# Nimble.net
KiCad netlist of a schematic drawn in EAGLE
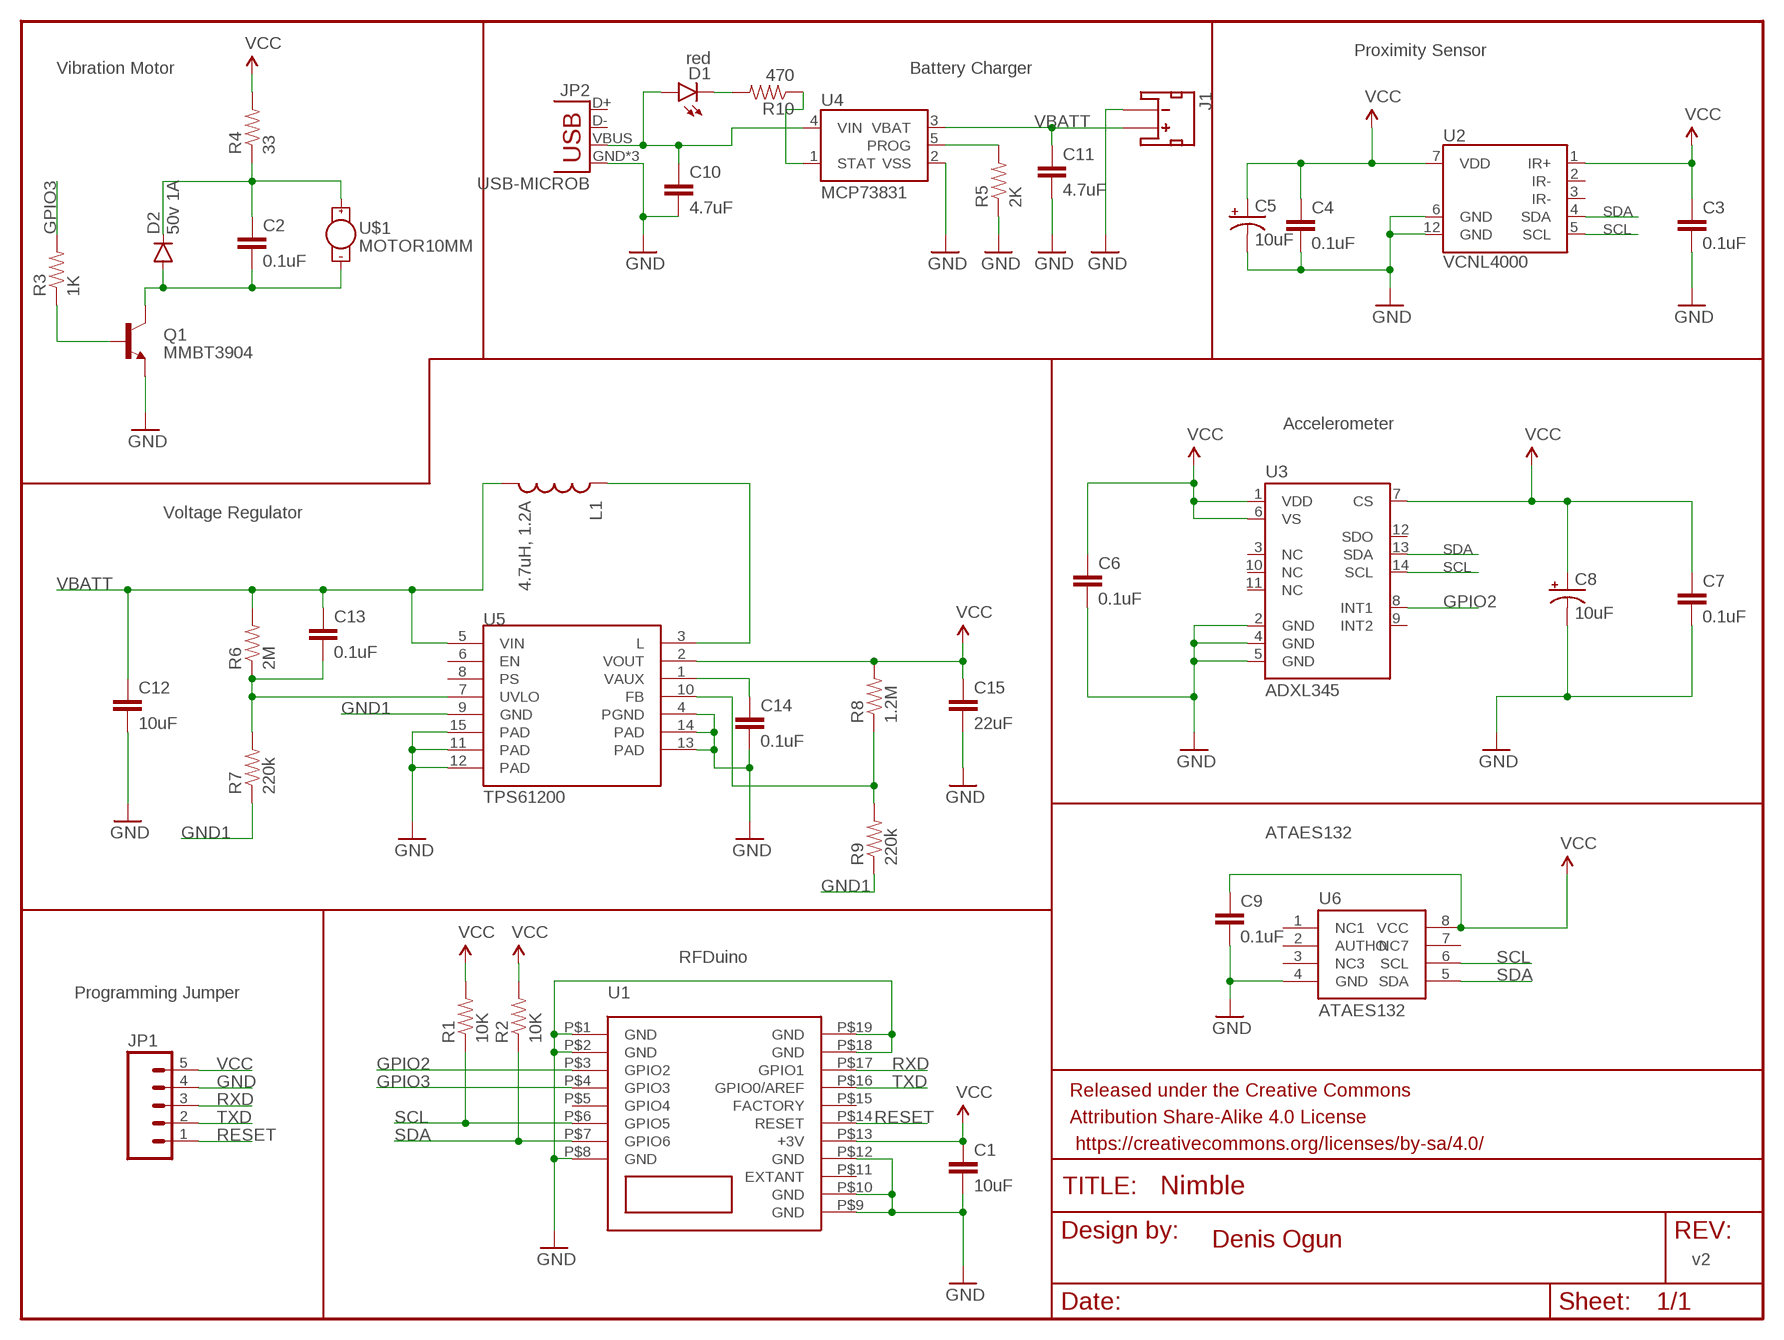
[diagram p0: schematic, sheet 1]

(export (version "E")
  (design (tool "Eeschema 10.0.6"))
  (components
    (comp (ref "C1")
      (value "10uF")
      (footprint "eagle-import:0603-CAP")
      (libsource (lib "eagle-import") (part "CAP0603-CAP"))
    )
    (comp (ref "C2")
      (value "0.1uF")
      (footprint "eagle-import:0603-CAP")
      (libsource (lib "eagle-import") (part "CAP0603-CAP"))
    )
    (comp (ref "C3")
      (value "0.1uF")
      (footprint "eagle-import:0603-CAP")
      (libsource (lib "eagle-import") (part "CAP0603-CAP"))
    )
    (comp (ref "C4")
      (value "0.1uF")
      (footprint "eagle-import:0603-CAP")
      (libsource (lib "eagle-import") (part "CAP0603-CAP"))
    )
    (comp (ref "C5")
      (value "10uF")
      (footprint "eagle-import:EIA3216")
      (libsource (lib "eagle-import") (part "CAP_POL1206"))
    )
    (comp (ref "C6")
      (value "0.1uF")
      (footprint "eagle-import:0603-CAP")
      (libsource (lib "eagle-import") (part "CAP0603-CAP"))
    )
    (comp (ref "C7")
      (value "0.1uF")
      (footprint "eagle-import:0603-CAP")
      (libsource (lib "eagle-import") (part "CAP0603-CAP"))
    )
    (comp (ref "C8")
      (value "10uF")
      (footprint "eagle-import:EIA3216")
      (libsource (lib "eagle-import") (part "CAP_POL1206"))
    )
    (comp (ref "C9")
      (value "0.1uF")
      (footprint "eagle-import:0603-CAP")
      (libsource (lib "eagle-import") (part "CAP0603-CAP"))
    )
    (comp (ref "C10")
      (value "4.7uF")
      (footprint "eagle-import:0603-CAP")
      (libsource (lib "eagle-import") (part "CAP0603-CAP"))
    )
    (comp (ref "C11")
      (value "4.7uF")
      (footprint "eagle-import:0603-CAP")
      (libsource (lib "eagle-import") (part "CAP0603-CAP"))
    )
    (comp (ref "C12")
      (value "10uF")
      (footprint "eagle-import:1206")
      (libsource (lib "eagle-import") (part "CAP1206"))
    )
    (comp (ref "C13")
      (value "0.1uF")
      (footprint "eagle-import:0603-CAP")
      (libsource (lib "eagle-import") (part "CAP0603-CAP"))
    )
    (comp (ref "C14")
      (value "0.1uF")
      (footprint "eagle-import:0603-CAP")
      (libsource (lib "eagle-import") (part "CAP0603-CAP"))
    )
    (comp (ref "C15")
      (value "22uF")
      (footprint "eagle-import:0805")
      (libsource (lib "eagle-import") (part "CAP0805"))
    )
    (comp (ref "D1")
      (value "red")
      (footprint "eagle-import:LED-0603")
      (libsource (lib "eagle-import") (part "LED0603"))
    )
    (comp (ref "D2")
      (value "50v 1A")
      (footprint "eagle-import:SMA-DIODE")
      (libsource (lib "eagle-import") (part "DIODESMA"))
    )
    (comp (ref "FRAME1")
      (value "FRAME-LETTERNO_PACKAGE")
      (footprint "eagle-import:DUMMY")
      (fields (field (name "DESIGNER") "Nobody"))
      (libsource (lib "eagle-import") (part "FRAME-LETTERNO_PACKAGE"))
    )
    (comp (ref "J1")
      (value "JST_2MM_MALE")
      (footprint "eagle-import:JST-2-SMD")
      (libsource (lib "eagle-import") (part "JST_2MM_MALE"))
    )
    (comp (ref "JP1")
      (value "M05PTH")
      (footprint "eagle-import:1X05")
      (libsource (lib "eagle-import") (part "M05PTH"))
    )
    (comp (ref "JP2")
      (value "USB-MICROB")
      (footprint "eagle-import:USB-MICROB")
      (libsource (lib "eagle-import") (part "USB-MICROB"))
    )
    (comp (ref "L1")
      (value "4.7uH, 1.2A")
      (footprint "eagle-import:CDRH2D09")
      (libsource (lib "eagle-import") (part "INDUCTOR."))
    )
    (comp (ref "Q1")
      (value "MMBT3904")
      (footprint "eagle-import:SOT23-3")
      (libsource (lib "eagle-import") (part "TRANSISTOR_NPNMMBT2222A"))
    )
    (comp (ref "R1")
      (value "10K")
      (footprint "eagle-import:0603-RES")
      (libsource (lib "eagle-import") (part "RESISTOR0603"))
    )
    (comp (ref "R2")
      (value "10K")
      (footprint "eagle-import:0603-RES")
      (libsource (lib "eagle-import") (part "RESISTOR0603"))
    )
    (comp (ref "R3")
      (value "1K")
      (footprint "eagle-import:0603-RES")
      (libsource (lib "eagle-import") (part "RESISTOR0603"))
    )
    (comp (ref "R4")
      (value "33")
      (footprint "eagle-import:0603-RES")
      (libsource (lib "eagle-import") (part "RESISTOR0603"))
    )
    (comp (ref "R5")
      (value "2K")
      (footprint "eagle-import:0603-RES")
      (libsource (lib "eagle-import") (part "RESISTOR0603"))
    )
    (comp (ref "R6")
      (value "2M")
      (footprint "eagle-import:0603-RES")
      (libsource (lib "eagle-import") (part "RESISTOR0603"))
    )
    (comp (ref "R7")
      (value "220k")
      (footprint "eagle-import:0603-RES")
      (libsource (lib "eagle-import") (part "RESISTOR0603"))
    )
    (comp (ref "R8")
      (value "1.2M")
      (footprint "eagle-import:0603-RES")
      (libsource (lib "eagle-import") (part "RESISTOR0603"))
    )
    (comp (ref "R9")
      (value "220k")
      (footprint "eagle-import:0603-RES")
      (libsource (lib "eagle-import") (part "RESISTOR0603"))
    )
    (comp (ref "R10")
      (value "470")
      (footprint "eagle-import:0603-RES")
      (libsource (lib "eagle-import") (part "RESISTOR0603"))
    )
    (comp (ref "U$1")
      (value "MOTOR10MM")
      (footprint "eagle-import:VIBE-MOTOR-10MM")
      (libsource (lib "eagle-import") (part "MOTOR10MM"))
    )
    (comp (ref "U1")
      (value "RFD22301")
      (footprint "eagle-import:RFD22301")
      (libsource (lib "eagle-import") (part "RFD22301"))
    )
    (comp (ref "U2")
      (value "VCNL4000")
      (footprint "eagle-import:VCNL4000")
      (libsource (lib "eagle-import") (part "VCNL4000"))
    )
    (comp (ref "U3")
      (value "ADXL345")
      (footprint "eagle-import:LGA14")
      (libsource (lib "eagle-import") (part "ADXL345"))
    )
    (comp (ref "U4")
      (value "MCP73831")
      (footprint "eagle-import:SOT23-5")
      (libsource (lib "eagle-import") (part "MCP73831"))
    )
    (comp (ref "U5")
      (value "TPS61200")
      (footprint "eagle-import:QFN-10_PAD")
      (libsource (lib "eagle-import") (part "TPS61200"))
    )
    (comp (ref "U6")
      (value "ATAES132")
      (footprint "eagle-import:SOIC8")
      (libsource (lib "eagle-import") (part "ATAES132"))
    )
  )
  (nets
    (net (code "1") (name "/GND1") (class "Default")
      (node (ref "R7") (pin "1") (pinfunction "1_1") (pintype "passive"))
      (node (ref "R9") (pin "1") (pinfunction "1_1") (pintype "passive"))
      (node (ref "U5") (pin "9") (pinfunction "GND_9") (pintype "power_in"))
    )
    (net (code "2") (name "/GPIO2") (class "Default")
      (node (ref "U1") (pin "P$3") (pinfunction "GPIO2_P$3") (pintype "bidirectional"))
      (node (ref "U3") (pin "8") (pinfunction "INT1_8") (pintype "bidirectional"))
    )
    (net (code "3") (name "/GPIO3") (class "Default")
      (node (ref "R3") (pin "2") (pinfunction "2_2") (pintype "passive"))
      (node (ref "U1") (pin "P$4") (pinfunction "GPIO3_P$4") (pintype "bidirectional"))
    )
    (net (code "4") (name "/RESET") (class "Default")
      (node (ref "JP1") (pin "1") (pinfunction "1_1") (pintype "passive"))
      (node (ref "U1") (pin "P$14") (pinfunction "RESET_P$14") (pintype "bidirectional"))
    )
    (net (code "5") (name "/RXD") (class "Default")
      (node (ref "JP1") (pin "3") (pinfunction "3_3") (pintype "passive"))
      (node (ref "U1") (pin "P$17") (pinfunction "GPIO1_P$17") (pintype "bidirectional"))
    )
    (net (code "6") (name "/SCL") (class "Default")
      (node (ref "R1") (pin "1") (pinfunction "1_1") (pintype "passive"))
      (node (ref "U1") (pin "P$6") (pinfunction "GPIO5_P$6") (pintype "bidirectional"))
      (node (ref "U2") (pin "5") (pinfunction "SCL_5") (pintype "bidirectional"))
      (node (ref "U3") (pin "14") (pinfunction "SCL_14") (pintype "bidirectional"))
      (node (ref "U6") (pin "6") (pinfunction "SCL_6") (pintype "bidirectional"))
    )
    (net (code "7") (name "/SDA") (class "Default")
      (node (ref "R2") (pin "1") (pinfunction "1_1") (pintype "passive"))
      (node (ref "U1") (pin "P$7") (pinfunction "GPIO6_P$7") (pintype "bidirectional"))
      (node (ref "U2") (pin "4") (pinfunction "SDA_4") (pintype "bidirectional"))
      (node (ref "U3") (pin "13") (pinfunction "SDA_13") (pintype "bidirectional"))
      (node (ref "U6") (pin "5") (pinfunction "SDA_5") (pintype "bidirectional"))
    )
    (net (code "8") (name "/TXD") (class "Default")
      (node (ref "JP1") (pin "2") (pinfunction "2_2") (pintype "passive"))
      (node (ref "U1") (pin "P$16") (pinfunction "GPIO0/AREF_P$16") (pintype "bidirectional"))
    )
    (net (code "9") (name "/VBATT") (class "Default")
      (node (ref "C11") (pin "1") (pinfunction "1_1") (pintype "passive"))
      (node (ref "C12") (pin "1") (pinfunction "1_1") (pintype "passive"))
      (node (ref "C13") (pin "1") (pinfunction "1_1") (pintype "passive"))
      (node (ref "J1") (pin "2") (pinfunction "+_2") (pintype "bidirectional"))
      (node (ref "L1") (pin "P$2") (pinfunction "2_P$2") (pintype "passive"))
      (node (ref "R6") (pin "2") (pinfunction "2_2") (pintype "passive"))
      (node (ref "U4") (pin "3") (pinfunction "VBAT_3") (pintype "power_in"))
      (node (ref "U5") (pin "5") (pinfunction "VIN_5") (pintype "power_in"))
    )
    (net (code "10") (name "GND") (class "Default")
      (node (ref "C1") (pin "2") (pinfunction "2_2") (pintype "passive"))
      (node (ref "C10") (pin "2") (pinfunction "2_2") (pintype "passive"))
      (node (ref "C11") (pin "2") (pinfunction "2_2") (pintype "passive"))
      (node (ref "C12") (pin "2") (pinfunction "2_2") (pintype "passive"))
      (node (ref "C14") (pin "2") (pinfunction "2_2") (pintype "passive"))
      (node (ref "C15") (pin "2") (pinfunction "2_2") (pintype "passive"))
      (node (ref "C3") (pin "2") (pinfunction "2_2") (pintype "passive"))
      (node (ref "C4") (pin "2") (pinfunction "2_2") (pintype "passive"))
      (node (ref "C5") (pin "C") (pinfunction "-_C") (pintype "passive"))
      (node (ref "C6") (pin "2") (pinfunction "2_2") (pintype "passive"))
      (node (ref "C7") (pin "2") (pinfunction "2_2") (pintype "passive"))
      (node (ref "C8") (pin "C") (pinfunction "-_C") (pintype "passive"))
      (node (ref "C9") (pin "2") (pinfunction "2_2") (pintype "passive"))
      (node (ref "J1") (pin "1") (pinfunction "-_1") (pintype "bidirectional"))
      (node (ref "JP1") (pin "4") (pinfunction "4_4") (pintype "passive"))
      (node (ref "JP2") (pin "GND") (pinfunction "GND_GND") (pintype "bidirectional"))
      (node (ref "JP2") (pin "MT1") (pinfunction "GND_MT1") (pintype "bidirectional"))
      (node (ref "JP2") (pin "MT2") (pinfunction "GND_MT2") (pintype "bidirectional"))
      (node (ref "Q1") (pin "2") (pinfunction "E_2") (pintype "passive"))
      (node (ref "R5") (pin "1") (pinfunction "1_1") (pintype "passive"))
      (node (ref "U1") (pin "P$1") (pinfunction "GND_P$1") (pintype "bidirectional"))
      (node (ref "U1") (pin "P$10") (pinfunction "GND_P$10") (pintype "bidirectional"))
      (node (ref "U1") (pin "P$12") (pinfunction "GND_P$12") (pintype "bidirectional"))
      (node (ref "U1") (pin "P$18") (pinfunction "GND_P$18") (pintype "bidirectional"))
      (node (ref "U1") (pin "P$19") (pinfunction "GND_P$19") (pintype "bidirectional"))
      (node (ref "U1") (pin "P$2") (pinfunction "GND_P$2") (pintype "bidirectional"))
      (node (ref "U1") (pin "P$8") (pinfunction "GND_P$8") (pintype "bidirectional"))
      (node (ref "U1") (pin "P$9") (pinfunction "GND_P$9") (pintype "bidirectional"))
      (node (ref "U2") (pin "12") (pinfunction "GND_12") (pintype "bidirectional"))
      (node (ref "U2") (pin "6") (pinfunction "GND_6") (pintype "bidirectional"))
      (node (ref "U3") (pin "2") (pinfunction "GND_2") (pintype "bidirectional"))
      (node (ref "U3") (pin "4") (pinfunction "GND_4") (pintype "bidirectional"))
      (node (ref "U3") (pin "5") (pinfunction "GND_5") (pintype "bidirectional"))
      (node (ref "U4") (pin "2") (pinfunction "VSS_2") (pintype "power_in"))
      (node (ref "U5") (pin "11") (pinfunction "PAD_11") (pintype "power_in"))
      (node (ref "U5") (pin "12") (pinfunction "PAD_12") (pintype "power_in"))
      (node (ref "U5") (pin "13") (pinfunction "PAD_13") (pintype "power_in"))
      (node (ref "U5") (pin "14") (pinfunction "PAD_14") (pintype "power_in"))
      (node (ref "U5") (pin "15") (pinfunction "PAD_15") (pintype "power_in"))
      (node (ref "U5") (pin "4") (pinfunction "PGND_4") (pintype "power_in"))
      (node (ref "U6") (pin "4") (pinfunction "GND_4") (pintype "power_in"))
    )
    (net (code "11") (name "Net-(C2-Pad1)") (class "Default")
      (node (ref "C2") (pin "1") (pinfunction "1_1") (pintype "passive"))
      (node (ref "D2") (pin "C") (pinfunction "C_C") (pintype "passive"))
      (node (ref "R4") (pin "1") (pinfunction "1_1") (pintype "passive"))
      (node (ref "U$1") (pin "+") (pinfunction "+_+") (pintype "bidirectional"))
    )
    (net (code "12") (name "Net-(D1-PadC)") (class "Default")
      (node (ref "D1") (pin "C") (pinfunction "C_C") (pintype "passive"))
      (node (ref "R10") (pin "2") (pinfunction "2_2") (pintype "passive"))
    )
    (net (code "13") (name "Net-(L1-1)") (class "Default")
      (node (ref "L1") (pin "P$1") (pinfunction "1_P$1") (pintype "passive"))
      (node (ref "U5") (pin "3") (pinfunction "L_3") (pintype "passive"))
    )
    (net (code "14") (name "Net-(Q1-B)") (class "Default")
      (node (ref "Q1") (pin "1") (pinfunction "B_1") (pintype "passive"))
      (node (ref "R3") (pin "1") (pinfunction "1_1") (pintype "passive"))
    )
    (net (code "15") (name "Net-(Q1-C)") (class "Default")
      (node (ref "C2") (pin "2") (pinfunction "2_2") (pintype "passive"))
      (node (ref "D2") (pin "A") (pinfunction "A_A") (pintype "passive"))
      (node (ref "Q1") (pin "3") (pinfunction "C_3") (pintype "passive"))
      (node (ref "U$1") (pin "-") (pinfunction "-_-") (pintype "bidirectional"))
    )
    (net (code "16") (name "Net-(U4-PROG)") (class "Default")
      (node (ref "R5") (pin "2") (pinfunction "2_2") (pintype "passive"))
      (node (ref "U4") (pin "5") (pinfunction "PROG_5") (pintype "input"))
    )
    (net (code "17") (name "Net-(U4-STAT)") (class "Default")
      (node (ref "R10") (pin "1") (pinfunction "1_1") (pintype "passive"))
      (node (ref "U4") (pin "1") (pinfunction "STAT_1") (pintype "output"))
    )
    (net (code "18") (name "Net-(U4-VIN)") (class "Default")
      (node (ref "C10") (pin "1") (pinfunction "1_1") (pintype "passive"))
      (node (ref "D1") (pin "A") (pinfunction "A_A") (pintype "passive"))
      (node (ref "JP2") (pin "VBUS") (pinfunction "VBUS_VBUS") (pintype "bidirectional"))
      (node (ref "U4") (pin "4") (pinfunction "VIN_4") (pintype "power_in"))
    )
    (net (code "19") (name "Net-(U5-FB)") (class "Default")
      (node (ref "R8") (pin "1") (pinfunction "1_1") (pintype "passive"))
      (node (ref "R9") (pin "2") (pinfunction "2_2") (pintype "passive"))
      (node (ref "U5") (pin "10") (pinfunction "FB_10") (pintype "passive"))
    )
    (net (code "20") (name "Net-(U5-UVLO)") (class "Default")
      (node (ref "C13") (pin "2") (pinfunction "2_2") (pintype "passive"))
      (node (ref "R6") (pin "1") (pinfunction "1_1") (pintype "passive"))
      (node (ref "R7") (pin "2") (pinfunction "2_2") (pintype "passive"))
      (node (ref "U5") (pin "7") (pinfunction "UVLO_7") (pintype "passive"))
    )
    (net (code "21") (name "Net-(U5-VAUX)") (class "Default")
      (node (ref "C14") (pin "1") (pinfunction "1_1") (pintype "passive"))
      (node (ref "U5") (pin "1") (pinfunction "VAUX_1") (pintype "passive"))
    )
    (net (code "22") (name "VCC") (class "Default")
      (node (ref "C1") (pin "1") (pinfunction "1_1") (pintype "passive"))
      (node (ref "C15") (pin "1") (pinfunction "1_1") (pintype "passive"))
      (node (ref "C3") (pin "1") (pinfunction "1_1") (pintype "passive"))
      (node (ref "C4") (pin "1") (pinfunction "1_1") (pintype "passive"))
      (node (ref "C5") (pin "A") (pinfunction "+_A") (pintype "passive"))
      (node (ref "C6") (pin "1") (pinfunction "1_1") (pintype "passive"))
      (node (ref "C7") (pin "1") (pinfunction "1_1") (pintype "passive"))
      (node (ref "C8") (pin "A") (pinfunction "+_A") (pintype "passive"))
      (node (ref "C9") (pin "1") (pinfunction "1_1") (pintype "passive"))
      (node (ref "JP1") (pin "5") (pinfunction "5_5") (pintype "passive"))
      (node (ref "R1") (pin "2") (pinfunction "2_2") (pintype "passive"))
      (node (ref "R2") (pin "2") (pinfunction "2_2") (pintype "passive"))
      (node (ref "R4") (pin "2") (pinfunction "2_2") (pintype "passive"))
      (node (ref "R8") (pin "2") (pinfunction "2_2") (pintype "passive"))
      (node (ref "U1") (pin "P$13") (pinfunction "+3V_P$13") (pintype "bidirectional"))
      (node (ref "U2") (pin "1") (pinfunction "IR+_1") (pintype "bidirectional"))
      (node (ref "U2") (pin "7") (pinfunction "VDD_7") (pintype "bidirectional"))
      (node (ref "U3") (pin "1") (pinfunction "VDD_1") (pintype "bidirectional"))
      (node (ref "U3") (pin "6") (pinfunction "VS_6") (pintype "bidirectional"))
      (node (ref "U3") (pin "7") (pinfunction "CS_7") (pintype "bidirectional"))
      (node (ref "U5") (pin "2") (pinfunction "VOUT_2") (pintype "passive"))
      (node (ref "U6") (pin "8") (pinfunction "VCC_8") (pintype "power_in"))
    )
    (net (code "23") (name "unconnected-(J1-PAD1-PadNC1)") (class "Default")
      (node (ref "J1") (pin "NC1") (pinfunction "PAD1_NC1") (pintype "bidirectional"))
    )
    (net (code "24") (name "unconnected-(J1-PAD2-PadNC2)") (class "Default")
      (node (ref "J1") (pin "NC2") (pinfunction "PAD2_NC2") (pintype "bidirectional"))
    )
    (net (code "25") (name "unconnected-(JP2-PadD+)") (class "Default")
      (node (ref "JP2") (pin "D+") (pinfunction "D+_D+") (pintype "bidirectional"))
    )
    (net (code "26") (name "unconnected-(JP2-PadD-)") (class "Default")
      (node (ref "JP2") (pin "D-") (pinfunction "D-_D-") (pintype "bidirectional"))
    )
    (net (code "27") (name "unconnected-(U1-EXTANT-PadP$11)") (class "Default")
      (node (ref "U1") (pin "P$11") (pinfunction "EXTANT_P$11") (pintype "bidirectional"))
    )
    (net (code "28") (name "unconnected-(U1-FACTORY-PadP$15)") (class "Default")
      (node (ref "U1") (pin "P$15") (pinfunction "FACTORY_P$15") (pintype "bidirectional"))
    )
    (net (code "29") (name "unconnected-(U1-GPIO4-PadP$5)") (class "Default")
      (node (ref "U1") (pin "P$5") (pinfunction "GPIO4_P$5") (pintype "bidirectional"))
    )
    (net (code "30") (name "unconnected-(U2-IR--Pad2)") (class "Default")
      (node (ref "U2") (pin "2") (pinfunction "IR-_2") (pintype "bidirectional"))
    )
    (net (code "31") (name "unconnected-(U2-IR--Pad3)") (class "Default")
      (node (ref "U2") (pin "3") (pinfunction "IR-_3") (pintype "bidirectional"))
    )
    (net (code "32") (name "unconnected-(U3-INT2-Pad9)") (class "Default")
      (node (ref "U3") (pin "9") (pinfunction "INT2_9") (pintype "bidirectional"))
    )
    (net (code "33") (name "unconnected-(U3-NC-Pad3)") (class "Default")
      (node (ref "U3") (pin "3") (pinfunction "NC_3") (pintype "bidirectional"))
    )
    (net (code "34") (name "unconnected-(U3-NC-Pad10)") (class "Default")
      (node (ref "U3") (pin "10") (pinfunction "NC_10") (pintype "bidirectional"))
    )
    (net (code "35") (name "unconnected-(U3-NC-Pad11)") (class "Default")
      (node (ref "U3") (pin "11") (pinfunction "NC_11") (pintype "bidirectional"))
    )
    (net (code "36") (name "unconnected-(U3-SDO-Pad12)") (class "Default")
      (node (ref "U3") (pin "12") (pinfunction "SDO_12") (pintype "bidirectional"))
    )
    (net (code "37") (name "unconnected-(U5-EN-Pad6)") (class "Default")
      (node (ref "U5") (pin "6") (pinfunction "EN_6") (pintype "input"))
    )
    (net (code "38") (name "unconnected-(U5-PS-Pad8)") (class "Default")
      (node (ref "U5") (pin "8") (pinfunction "PS_8") (pintype "input"))
    )
    (net (code "39") (name "unconnected-(U6-AUTHO-Pad2)") (class "Default")
      (node (ref "U6") (pin "2") (pinfunction "AUTHO_2") (pintype "bidirectional"))
    )
    (net (code "40") (name "unconnected-(U6-NC1-Pad1)") (class "Default")
      (node (ref "U6") (pin "1") (pinfunction "NC1_1") (pintype "no_connect"))
    )
    (net (code "41") (name "unconnected-(U6-NC3-Pad3)") (class "Default")
      (node (ref "U6") (pin "3") (pinfunction "NC3_3") (pintype "no_connect"))
    )
    (net (code "42") (name "unconnected-(U6-NC7-Pad7)") (class "Default")
      (node (ref "U6") (pin "7") (pinfunction "NC7_7") (pintype "no_connect"))
    )
  )
)
